# Thermocouple_Digitizer.net
KiCad netlist of a schematic drawn in EAGLE
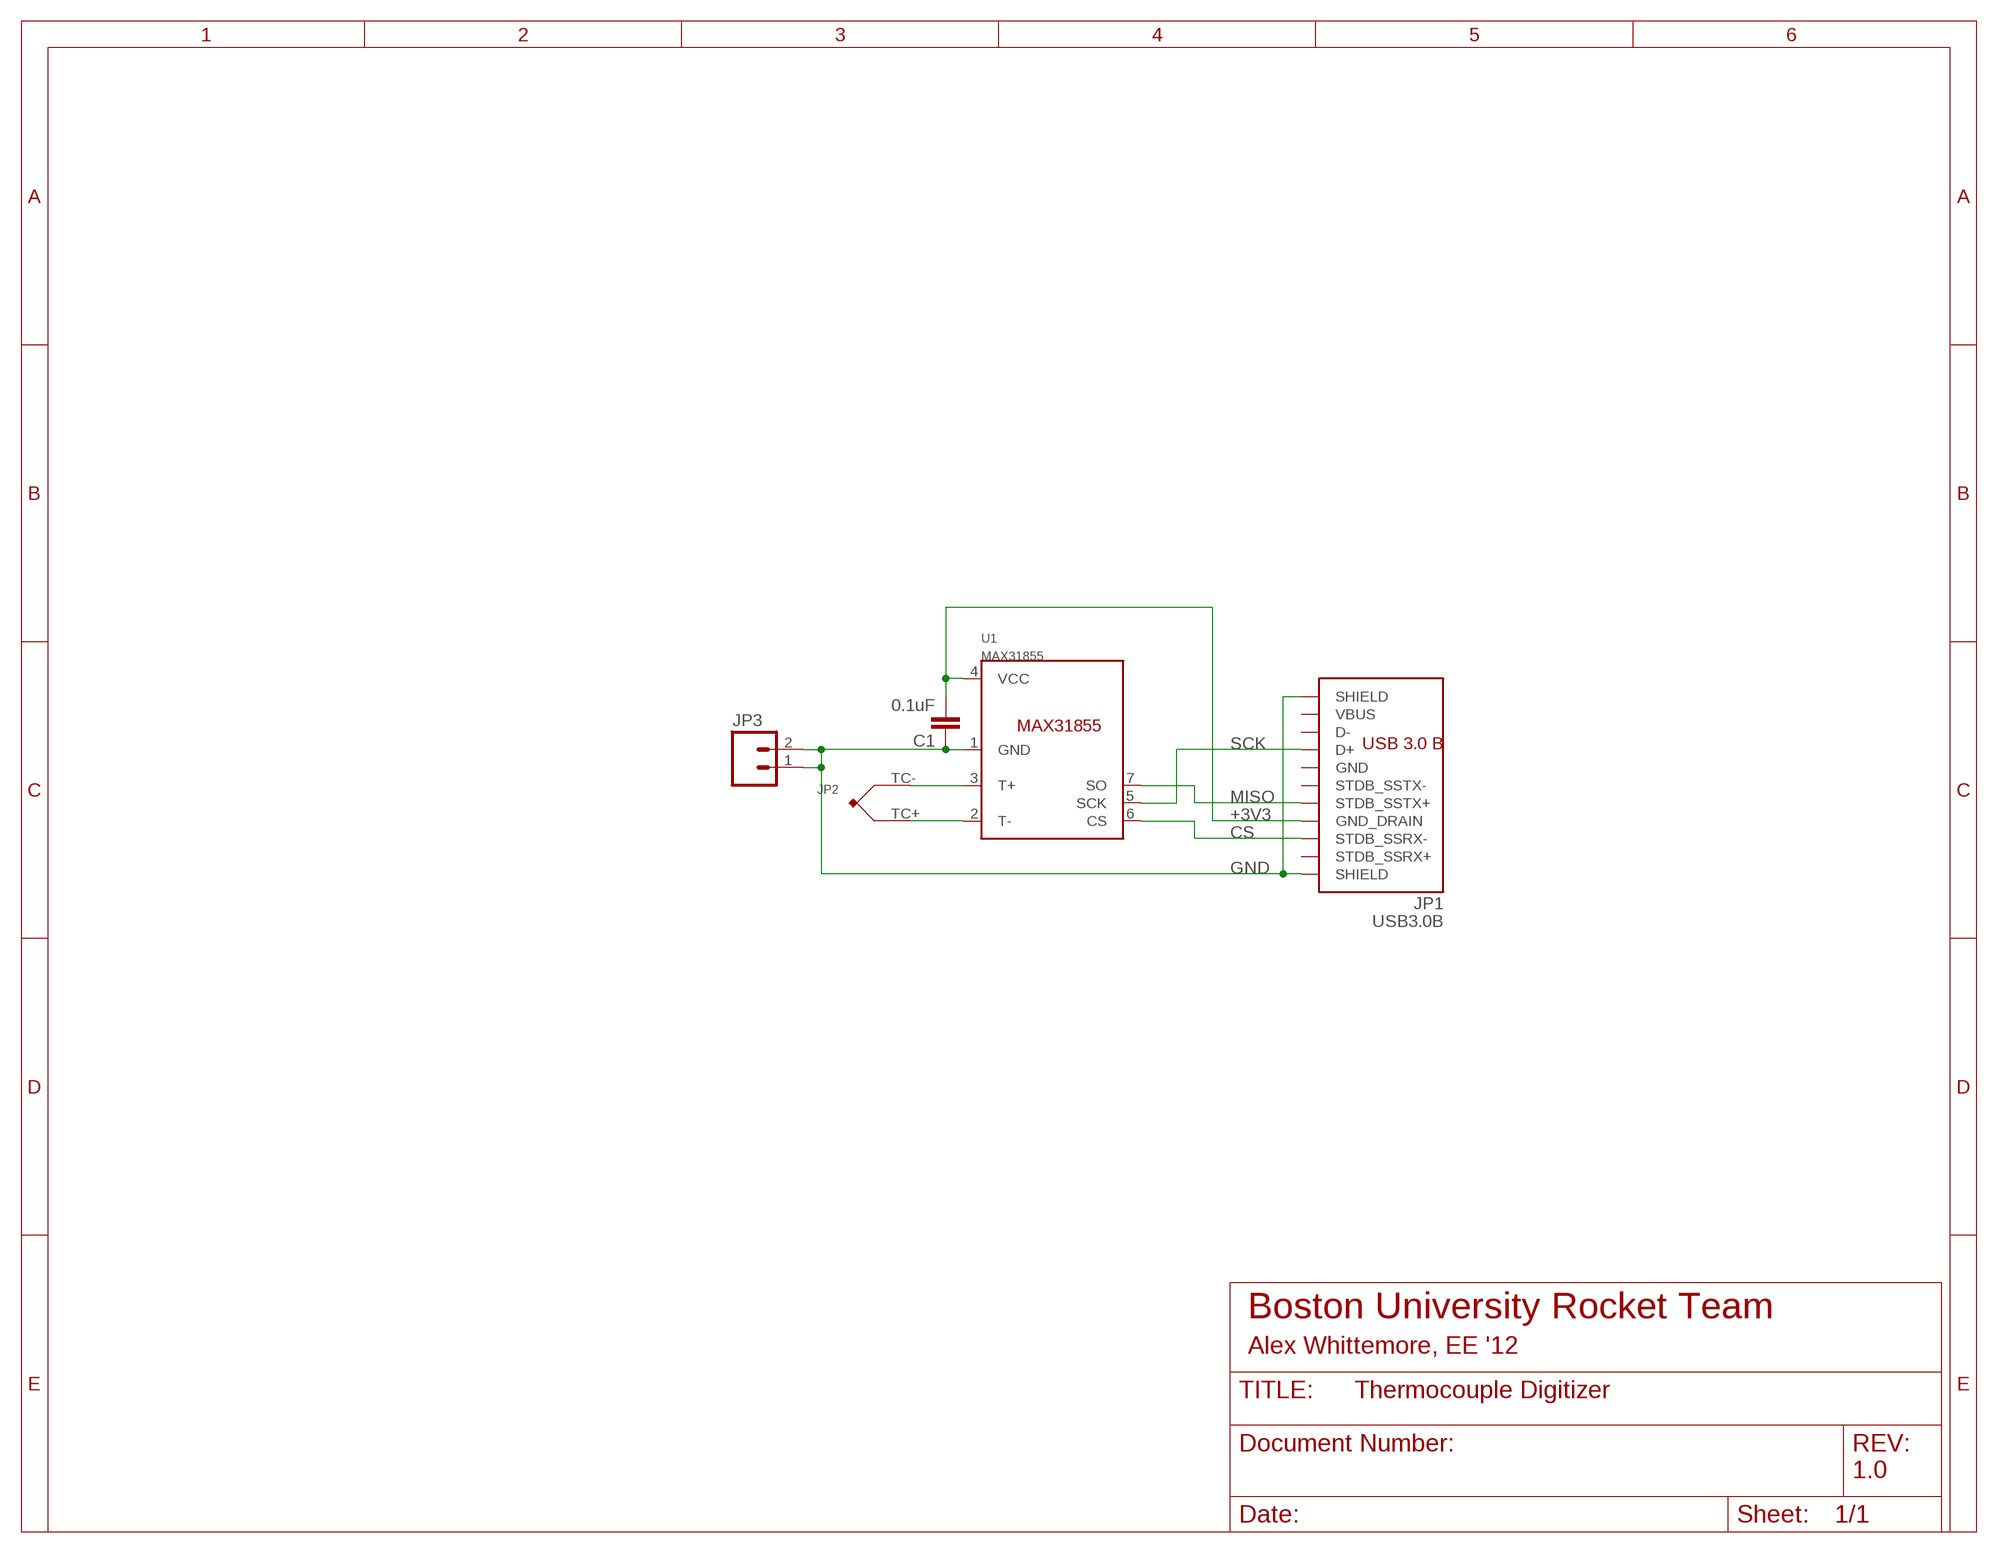
[diagram p0: schematic, sheet 1]

(export (version "E")
  (design (tool "Eeschema 10.0.6"))
  (components
    (comp (ref "C1")
      (value "0.1uF")
      (footprint "eagle-import:0402-CAP")
      (libsource (lib "eagle-import") (part "CAP0402-CAP"))
    )
    (comp (ref "JP1")
      (value "USB3.0B")
      (footprint "eagle-import:AMPHENOLUSB3.0B")
      (libsource (lib "eagle-import") (part "USB3.0B"))
    )
    (comp (ref "JP2")
      (value "OMEGA_PCC-SMP")
      (footprint "eagle-import:OMEGA_PCC-SMP")
      (libsource (lib "eagle-import") (part "OMEGA_PCC-SMP"))
    )
    (comp (ref "JP3")
      (value "M025MM")
      (footprint "eagle-import:SCREWTERMINAL-5MM-2")
      (libsource (lib "eagle-import") (part "M025MM"))
    )
    (comp (ref "U1")
      (value "MAX31855")
      (footprint "eagle-import:SOIC8")
      (libsource (lib "eagle-import") (part "MAX31855"))
    )
  )
  (nets
    (net (code "1") (name "/+3V3") (class "Default")
      (node (ref "C1") (pin "2") (pinfunction "2_2") (pintype "passive"))
      (node (ref "JP1") (pin "7") (pinfunction "GND_DRAIN_7") (pintype "bidirectional"))
      (node (ref "U1") (pin "4") (pinfunction "VCC_4") (pintype "power_in"))
    )
    (net (code "2") (name "/CS") (class "Default")
      (node (ref "JP1") (pin "8") (pinfunction "STDB_SSRX-_8") (pintype "bidirectional"))
      (node (ref "U1") (pin "6") (pinfunction "CS_6") (pintype "input"))
    )
    (net (code "3") (name "/GND") (class "Default")
      (node (ref "C1") (pin "1") (pinfunction "1_1") (pintype "passive"))
      (node (ref "JP1") (pin "10@1") (pinfunction "SHIELD_10@1") (pintype "bidirectional"))
      (node (ref "JP1") (pin "10@2") (pinfunction "SHIELD_10@2") (pintype "bidirectional"))
      (node (ref "JP3") (pin "1") (pinfunction "1_1") (pintype "passive"))
      (node (ref "JP3") (pin "2") (pinfunction "2_2") (pintype "passive"))
      (node (ref "U1") (pin "1") (pinfunction "GND_1") (pintype "power_in"))
    )
    (net (code "4") (name "/MISO") (class "Default")
      (node (ref "JP1") (pin "6") (pinfunction "STDB_SSTX+_6") (pintype "bidirectional"))
      (node (ref "U1") (pin "7") (pinfunction "SO_7") (pintype "output"))
    )
    (net (code "5") (name "/SCK") (class "Default")
      (node (ref "JP1") (pin "3") (pinfunction "D+_3") (pintype "bidirectional"))
      (node (ref "U1") (pin "5") (pinfunction "SCK_5") (pintype "input"))
    )
    (net (code "6") (name "Net-(U1-T+)") (class "Default")
      (node (ref "JP2") (pin "TC-") (pinfunction "TC-_TC-") (pintype "output"))
      (node (ref "U1") (pin "3") (pinfunction "T+_3") (pintype "input"))
    )
    (net (code "7") (name "Net-(U1-T-)") (class "Default")
      (node (ref "JP2") (pin "TC+") (pinfunction "TC+_TC+") (pintype "output"))
      (node (ref "U1") (pin "2") (pinfunction "T-_2") (pintype "input"))
    )
    (net (code "8") (name "unconnected-(JP1-D--Pad2)") (class "Default")
      (node (ref "JP1") (pin "2") (pinfunction "D-_2") (pintype "bidirectional"))
    )
    (net (code "9") (name "unconnected-(JP1-GND-Pad4)") (class "Default")
      (node (ref "JP1") (pin "4") (pinfunction "GND_4") (pintype "bidirectional"))
    )
    (net (code "10") (name "unconnected-(JP1-STDB_SSRX+-Pad9)") (class "Default")
      (node (ref "JP1") (pin "9") (pinfunction "STDB_SSRX+_9") (pintype "bidirectional"))
    )
    (net (code "11") (name "unconnected-(JP1-STDB_SSTX--Pad5)") (class "Default")
      (node (ref "JP1") (pin "5") (pinfunction "STDB_SSTX-_5") (pintype "bidirectional"))
    )
    (net (code "12") (name "unconnected-(JP1-VBUS-Pad1)") (class "Default")
      (node (ref "JP1") (pin "1") (pinfunction "VBUS_1") (pintype "bidirectional"))
    )
  )
)
